# ESR_NM8032.net
KiCad netlist of a schematic drawn in EAGLE
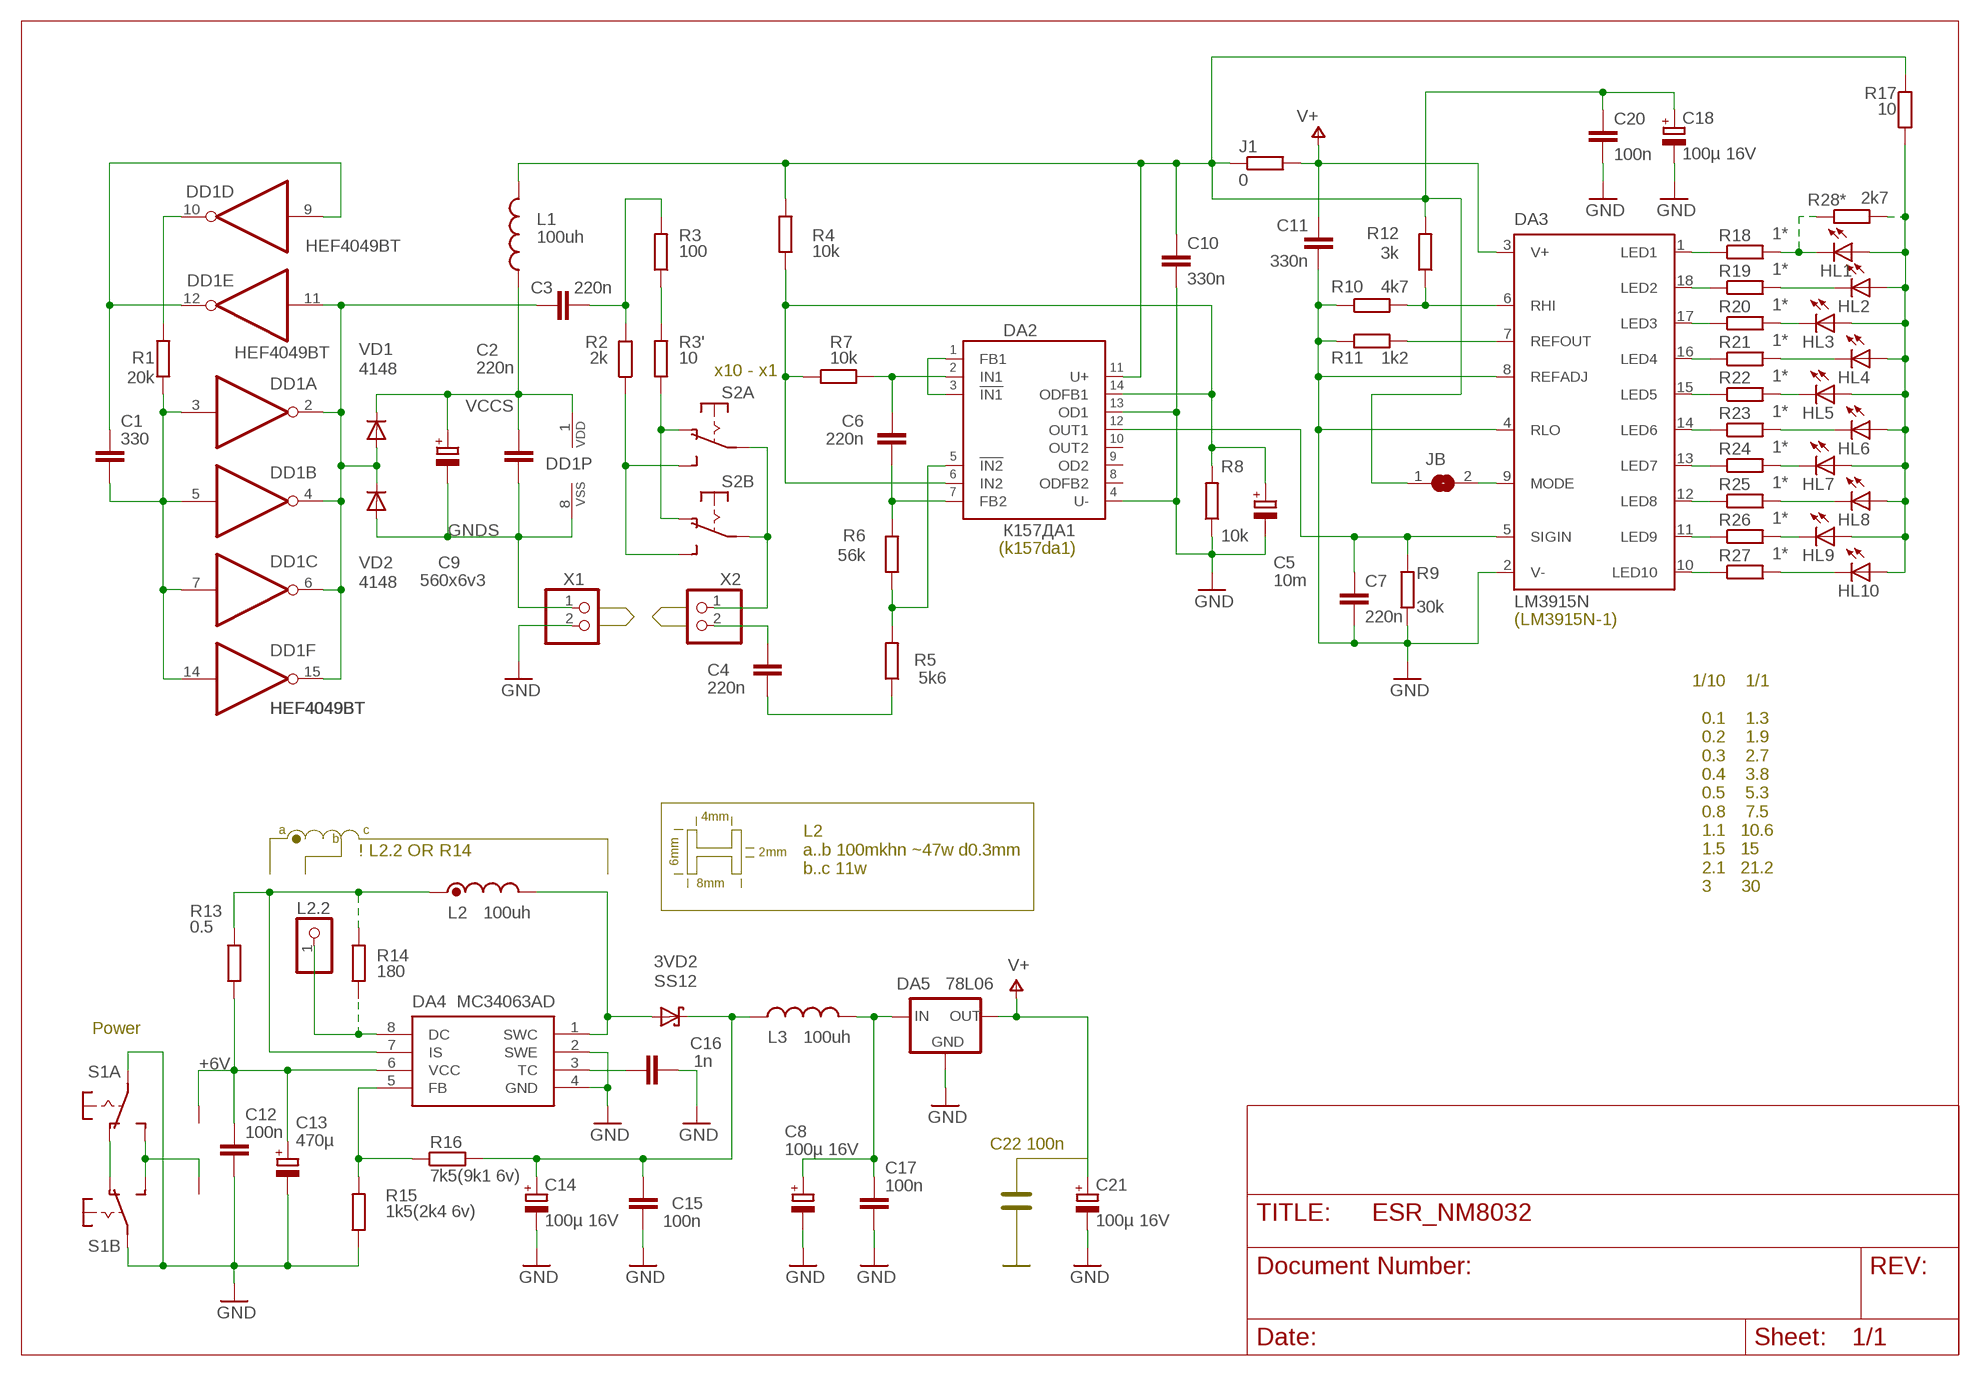
[diagram p0: schematic, sheet 1]

(export (version "E")
  (design (tool "Eeschema 10.0.6"))
  (components
    (comp (ref "3VD2")
      (value "SS12")
      (footprint "eagle-import:SMB")
      (libsource (lib "eagle-import") (part "SCHOTTKY-DIODESMD"))
    )
    (comp (ref "C1")
      (value "330")
      (footprint "eagle-import:C0805")
      (libsource (lib "eagle-import") (part "rcl_C-EUC0805"))
    )
    (comp (ref "C2")
      (value "220n")
      (footprint "eagle-import:C075-032X103")
      (libsource (lib "eagle-import") (part "rcl_C-EU075-032X103"))
    )
    (comp (ref "C3")
      (value "220n")
      (footprint "eagle-import:C0805")
      (libsource (lib "eagle-import") (part "rcl_C-EUC0805"))
    )
    (comp (ref "C4")
      (value "220n")
      (footprint "eagle-import:C0805")
      (libsource (lib "eagle-import") (part "rcl_C-EUC0805"))
    )
    (comp (ref "C5")
      (value "10m")
      (footprint "eagle-import:E2-5")
      (libsource (lib "eagle-import") (part "CPOL-EUE2-5"))
    )
    (comp (ref "C6")
      (value "220n")
      (footprint "eagle-import:C075-032X103")
      (libsource (lib "eagle-import") (part "rcl_C-EU075-032X103"))
    )
    (comp (ref "C7")
      (value "220n")
      (footprint "eagle-import:C0805")
      (libsource (lib "eagle-import") (part "rcl_C-EUC0805"))
    )
    (comp (ref "C8")
      (value "100µ 16V")
      (footprint "eagle-import:RCL_E2,5-5")
      (libsource (lib "eagle-import") (part "RCL_CPOL-EUE2.5-5"))
    )
    (comp (ref "C9")
      (value "560x6v3")
      (footprint "eagle-import:HWPROGUSB_RCL_E3,5-8")
      (libsource (lib "eagle-import") (part "HWPROGUSB_RCL_CPOL-EUE3.5-8"))
    )
    (comp (ref "C10")
      (value "330n")
      (footprint "eagle-import:C0805")
      (libsource (lib "eagle-import") (part "rcl_C-EUC0805"))
    )
    (comp (ref "C11")
      (value "330n")
      (footprint "eagle-import:C0805")
      (libsource (lib "eagle-import") (part "rcl_C-EUC0805"))
    )
    (comp (ref "C12")
      (value "100n")
      (footprint "eagle-import:C0805")
      (libsource (lib "eagle-import") (part "C-EUC0805"))
    )
    (comp (ref "C13")
      (value "470µ")
      (footprint "eagle-import:RCL_E2,5-7")
      (libsource (lib "eagle-import") (part "RCL_CPOL-EUE2.5-7"))
    )
    (comp (ref "C14")
      (value "100µ 16V")
      (footprint "eagle-import:RCL_E2,5-5")
      (libsource (lib "eagle-import") (part "RCL_CPOL-EUE2.5-5"))
    )
    (comp (ref "C15")
      (value "100n")
      (footprint "eagle-import:C0805")
      (libsource (lib "eagle-import") (part "rcl_C-EUC0805"))
    )
    (comp (ref "C16")
      (value "1n")
      (footprint "eagle-import:C0805")
      (libsource (lib "eagle-import") (part "rcl_C-EUC0805"))
    )
    (comp (ref "C17")
      (value "100n")
      (footprint "eagle-import:C0805")
      (libsource (lib "eagle-import") (part "rcl_C-EUC0805"))
    )
    (comp (ref "C18")
      (value "100µ 16V")
      (footprint "eagle-import:RCL_E2,5-5")
      (libsource (lib "eagle-import") (part "RCL_CPOL-EUE2.5-5"))
    )
    (comp (ref "C20")
      (value "100n")
      (footprint "eagle-import:C0805")
      (libsource (lib "eagle-import") (part "rcl_C-EUC0805"))
    )
    (comp (ref "C21")
      (value "100µ 16V")
      (footprint "eagle-import:RCL_E2,5-5")
      (libsource (lib "eagle-import") (part "RCL_CPOL-EUE2.5-5"))
    )
    (comp (ref "DA2")
      (value "К157ДА1")
      (footprint "eagle-import:DIL14")
      (libsource (lib "eagle-import") (part "K157DA1"))
    )
    (comp (ref "DA3")
      (value "LM3915N")
      (footprint "eagle-import:DIL18")
      (libsource (lib "eagle-import") (part "LM391N5"))
    )
    (comp (ref "DA4")
      (value "MC34063AD")
      (footprint "eagle-import:SOIC8")
      (libsource (lib "eagle-import") (part "MC34063AD"))
    )
    (comp (ref "DA5")
      (value "78L06")
      (footprint "eagle-import:SOT89R")
      (libsource (lib "eagle-import") (part "78LXX_SOT89"))
    )
    (comp (ref "DD1")
      (value "HEF4049BT")
      (footprint "eagle-import:SO16")
      (libsource (lib "eagle-import") (part "4049D"))
    )
    (comp (ref "HL1")
      (value "LED3MM")
      (footprint "eagle-import:LED3MM")
      (libsource (lib "eagle-import") (part "LED3MM"))
    )
    (comp (ref "HL2")
      (value "LED3MM")
      (footprint "eagle-import:LED3MM")
      (libsource (lib "eagle-import") (part "LED3MM"))
    )
    (comp (ref "HL3")
      (value "LED3MM")
      (footprint "eagle-import:LED3MM")
      (libsource (lib "eagle-import") (part "LED3MM"))
    )
    (comp (ref "HL4")
      (value "LED3MM")
      (footprint "eagle-import:LED3MM")
      (libsource (lib "eagle-import") (part "LED3MM"))
    )
    (comp (ref "HL5")
      (value "LED3MM")
      (footprint "eagle-import:LED3MM")
      (libsource (lib "eagle-import") (part "LED3MM"))
    )
    (comp (ref "HL6")
      (value "LED3MM")
      (footprint "eagle-import:LED3MM")
      (libsource (lib "eagle-import") (part "LED3MM"))
    )
    (comp (ref "HL7")
      (value "LED3MM")
      (footprint "eagle-import:LED3MM")
      (libsource (lib "eagle-import") (part "LED3MM"))
    )
    (comp (ref "HL8")
      (value "LED3MM")
      (footprint "eagle-import:LED3MM")
      (libsource (lib "eagle-import") (part "LED3MM"))
    )
    (comp (ref "HL9")
      (value "LED3MM")
      (footprint "eagle-import:LED3MM")
      (libsource (lib "eagle-import") (part "LED3MM"))
    )
    (comp (ref "HL10")
      (value "LED3MM")
      (footprint "eagle-import:LED3MM")
      (libsource (lib "eagle-import") (part "LED3MM"))
    )
    (comp (ref "J1")
      (value "0")
      (footprint "eagle-import:R1206W")
      (libsource (lib "eagle-import") (part "R-EU_R1206W"))
    )
    (comp (ref "JB") (value "SJ") (footprint "eagle-import:SJ") (libsource (lib "eagle-import") (part "SJ")))
    (comp (ref "L1")
      (value "100uh")
      (footprint "eagle-import:0207_10")
      (libsource (lib "eagle-import") (part "L-US0207/10"))
    )
    (comp (ref "L2")
      (value "100uh")
      (footprint "eagle-import:0204_7")
      (libsource (lib "eagle-import") (part "L-US0204/7"))
    )
    (comp (ref "L2.2")
      (value "PINHD-1X1")
      (footprint "eagle-import:1X01")
      (libsource (lib "eagle-import") (part "PINHD-1X1"))
    )
    (comp (ref "L3")
      (value "100uh")
      (footprint "eagle-import:0207_10")
      (libsource (lib "eagle-import") (part "L-US0207/10"))
    )
    (comp (ref "R1")
      (value "20k")
      (footprint "eagle-import:M0805")
      (libsource (lib "eagle-import") (part "R-EU_M0805"))
    )
    (comp (ref "R2")
      (value "2k")
      (footprint "eagle-import:M0805")
      (libsource (lib "eagle-import") (part "R-EU_M0805"))
    )
    (comp (ref "R3")
      (value "100")
      (footprint "eagle-import:M0805")
      (libsource (lib "eagle-import") (part "R-EU_M0805"))
    )
    (comp (ref "R3'")
      (value "10")
      (footprint "eagle-import:M0805")
      (libsource (lib "eagle-import") (part "R-EU_M0805"))
    )
    (comp (ref "R4")
      (value "10k")
      (footprint "eagle-import:R0805")
      (libsource (lib "eagle-import") (part "R-EU_R0805"))
    )
    (comp (ref "R5")
      (value "5k6")
      (footprint "eagle-import:M0805")
      (libsource (lib "eagle-import") (part "R-EU_M0805"))
    )
    (comp (ref "R6")
      (value "56k")
      (footprint "eagle-import:R0805")
      (libsource (lib "eagle-import") (part "R-EU_R0805"))
    )
    (comp (ref "R7")
      (value "10k")
      (footprint "eagle-import:R0805")
      (libsource (lib "eagle-import") (part "R-EU_R0805"))
    )
    (comp (ref "R8")
      (value "10k")
      (footprint "eagle-import:R0805")
      (libsource (lib "eagle-import") (part "R-EU_R0805"))
    )
    (comp (ref "R9")
      (value "30k")
      (footprint "eagle-import:R0805")
      (libsource (lib "eagle-import") (part "R-EU_R0805"))
    )
    (comp (ref "R10")
      (value "4k7")
      (footprint "eagle-import:R0805")
      (libsource (lib "eagle-import") (part "R-EU_R0805"))
    )
    (comp (ref "R11")
      (value "1k2")
      (footprint "eagle-import:R0805")
      (libsource (lib "eagle-import") (part "R-EU_R0805"))
    )
    (comp (ref "R12")
      (value "3k")
      (footprint "eagle-import:R0805")
      (libsource (lib "eagle-import") (part "R-EU_R0805"))
    )
    (comp (ref "R13")
      (value "0.5")
      (footprint "eagle-import:M1206")
      (libsource (lib "eagle-import") (part "R-EU_M1206"))
    )
    (comp (ref "R14")
      (value "180")
      (footprint "eagle-import:M0805")
      (libsource (lib "eagle-import") (part "R-EU_M0805"))
    )
    (comp (ref "R15")
      (value "1k5(2k4 6v)")
      (footprint "eagle-import:M0805")
      (libsource (lib "eagle-import") (part "R-EU_M0805"))
    )
    (comp (ref "R16")
      (value "7k5(9k1 6v)")
      (footprint "eagle-import:M0805")
      (libsource (lib "eagle-import") (part "R-EU_M0805"))
    )
    (comp (ref "R17")
      (value "10")
      (footprint "eagle-import:R0805")
      (libsource (lib "eagle-import") (part "R-EU_R0805"))
    )
    (comp (ref "R18")
      (value "1*")
      (footprint "eagle-import:R0805")
      (libsource (lib "eagle-import") (part "R-EU_R0805"))
    )
    (comp (ref "R19")
      (value "1*")
      (footprint "eagle-import:R0805")
      (libsource (lib "eagle-import") (part "R-EU_R0805"))
    )
    (comp (ref "R20")
      (value "1*")
      (footprint "eagle-import:R0805")
      (libsource (lib "eagle-import") (part "R-EU_R0805"))
    )
    (comp (ref "R21")
      (value "1*")
      (footprint "eagle-import:R0805")
      (libsource (lib "eagle-import") (part "R-EU_R0805"))
    )
    (comp (ref "R22")
      (value "1*")
      (footprint "eagle-import:R0805")
      (libsource (lib "eagle-import") (part "R-EU_R0805"))
    )
    (comp (ref "R23")
      (value "1*")
      (footprint "eagle-import:R0805")
      (libsource (lib "eagle-import") (part "R-EU_R0805"))
    )
    (comp (ref "R24")
      (value "1*")
      (footprint "eagle-import:R0805")
      (libsource (lib "eagle-import") (part "R-EU_R0805"))
    )
    (comp (ref "R25")
      (value "1*")
      (footprint "eagle-import:R0805")
      (libsource (lib "eagle-import") (part "R-EU_R0805"))
    )
    (comp (ref "R26")
      (value "1*")
      (footprint "eagle-import:R0805")
      (libsource (lib "eagle-import") (part "R-EU_R0805"))
    )
    (comp (ref "R27")
      (value "1*")
      (footprint "eagle-import:R0805")
      (libsource (lib "eagle-import") (part "R-EU_R0805"))
    )
    (comp (ref "R28*")
      (value "2k7")
      (footprint "eagle-import:R0805")
      (libsource (lib "eagle-import") (part "R-EU_R0805"))
    )
    (comp (ref "S1")
      (value "SWITCH9X4")
      (footprint "eagle-import:SWITCH9X4")
      (libsource (lib "eagle-import") (part "SWITCH9X4"))
    )
    (comp (ref "S2")
      (value "SWITCH9X4")
      (footprint "eagle-import:SWITCH9X4")
      (libsource (lib "eagle-import") (part "SWITCH9X4"))
    )
    (comp (ref "U$2") (value "B-") (footprint "eagle-import:B-") (libsource (lib "eagle-import") (part "B-")))
    (comp (ref "U$4") (value "B+") (footprint "eagle-import:B+") (libsource (lib "eagle-import") (part "B+")))
    (comp (ref "VD1")
      (value "4148")
      (footprint "eagle-import:SOD80C")
      (libsource (lib "eagle-import") (part "DIODE-SOD80C"))
    )
    (comp (ref "VD2")
      (value "4148")
      (footprint "eagle-import:SOD80C")
      (libsource (lib "eagle-import") (part "DIODE-SOD80C"))
    )
    (comp (ref "X1")
      (value "PINHD-1X2/2")
      (footprint "eagle-import:1X02")
      (libsource (lib "eagle-import") (part "PINHD-1X2/2"))
    )
    (comp (ref "X2")
      (value "PINHD-1X2/2")
      (footprint "eagle-import:1X02")
      (libsource (lib "eagle-import") (part "PINHD-1X2/2"))
    )
  )
  (nets
    (net (code "1") (name "/+6V") (class "Default")
      (node (ref "C12") (pin "1") (pinfunction "1_1") (pintype "passive"))
      (node (ref "C13") (pin "+") (pinfunction "+_+") (pintype "passive"))
      (node (ref "DA4") (pin "6") (pinfunction "VCC_6") (pintype "passive"))
      (node (ref "R13") (pin "1") (pinfunction "1_1") (pintype "passive"))
      (node (ref "U$4") (pin "P$1") (pinfunction "P$1_P$1") (pintype "bidirectional"))
    )
    (net (code "2") (name "/GNDS") (class "Default")
      (node (ref "C2") (pin "2") (pinfunction "2_2") (pintype "passive"))
      (node (ref "C9") (pin "-") (pinfunction "-_-") (pintype "passive"))
      (node (ref "DD1") (pin "8") (pinfunction "VSS_8") (pintype "power_in"))
      (node (ref "VD2") (pin "A") (pinfunction "A_A") (pintype "passive"))
      (node (ref "X1") (pin "1") (pinfunction "1_1") (pintype "passive"))
    )
    (net (code "3") (name "/VCCS") (class "Default")
      (node (ref "C2") (pin "1") (pinfunction "1_1") (pintype "passive"))
      (node (ref "C9") (pin "+") (pinfunction "+_+") (pintype "passive"))
      (node (ref "DD1") (pin "1") (pinfunction "VDD_1") (pintype "power_in"))
      (node (ref "L1") (pin "1") (pinfunction "1_1") (pintype "passive"))
      (node (ref "VD1") (pin "C") (pinfunction "C_C") (pintype "passive"))
    )
    (net (code "4") (name "GND") (class "Default")
      (node (ref "C10") (pin "2") (pinfunction "2_2") (pintype "passive"))
      (node (ref "C11") (pin "2") (pinfunction "2_2") (pintype "passive"))
      (node (ref "C12") (pin "2") (pinfunction "2_2") (pintype "passive"))
      (node (ref "C13") (pin "-") (pinfunction "-_-") (pintype "passive"))
      (node (ref "C14") (pin "-") (pinfunction "-_-") (pintype "passive"))
      (node (ref "C15") (pin "1") (pinfunction "1_1") (pintype "passive"))
      (node (ref "C16") (pin "2") (pinfunction "2_2") (pintype "passive"))
      (node (ref "C17") (pin "2") (pinfunction "2_2") (pintype "passive"))
      (node (ref "C18") (pin "-") (pinfunction "-_-") (pintype "passive"))
      (node (ref "C20") (pin "2") (pinfunction "2_2") (pintype "passive"))
      (node (ref "C21") (pin "-") (pinfunction "-_-") (pintype "passive"))
      (node (ref "C5") (pin "-") (pinfunction "-_-") (pintype "passive"))
      (node (ref "C7") (pin "2") (pinfunction "2_2") (pintype "passive"))
      (node (ref "C8") (pin "-") (pinfunction "-_-") (pintype "passive"))
      (node (ref "DA2") (pin "13") (pinfunction "OD1_13") (pintype "passive"))
      (node (ref "DA2") (pin "4") (pinfunction "U-_4") (pintype "passive"))
      (node (ref "DA3") (pin "2") (pinfunction "V-_2") (pintype "power_in"))
      (node (ref "DA3") (pin "4") (pinfunction "RLO_4") (pintype "input"))
      (node (ref "DA3") (pin "8") (pinfunction "REFADJ_8") (pintype "passive"))
      (node (ref "DA4") (pin "2") (pinfunction "SWE_2") (pintype "passive"))
      (node (ref "DA4") (pin "4") (pinfunction "GND_4") (pintype "passive"))
      (node (ref "DA5") (pin "3") (pinfunction "GND_3") (pintype "input"))
      (node (ref "DA5") (pin "4") (pinfunction "GND_4") (pintype "input"))
      (node (ref "R10") (pin "1") (pinfunction "1_1") (pintype "passive"))
      (node (ref "R11") (pin "1") (pinfunction "1_1") (pintype "passive"))
      (node (ref "R15") (pin "1") (pinfunction "1_1") (pintype "passive"))
      (node (ref "R8") (pin "1") (pinfunction "1_1") (pintype "passive"))
      (node (ref "R9") (pin "1") (pinfunction "1_1") (pintype "passive"))
      (node (ref "S1") (pin "10") (pinfunction "P_10") (pintype "passive"))
      (node (ref "S1") (pin "20") (pinfunction "P_20") (pintype "passive"))
      (node (ref "X1") (pin "2") (pinfunction "2_2") (pintype "passive"))
    )
    (net (code "5") (name "Net-(3VD2-PadC)") (class "Default")
      (node (ref "3VD2") (pin "C") (pinfunction "C_C") (pintype "passive"))
      (node (ref "C14") (pin "+") (pinfunction "+_+") (pintype "passive"))
      (node (ref "C15") (pin "2") (pinfunction "2_2") (pintype "passive"))
      (node (ref "L3") (pin "1") (pinfunction "1_1") (pintype "passive"))
      (node (ref "R16") (pin "2") (pinfunction "2_2") (pintype "passive"))
    )
    (net (code "6") (name "Net-(C3-Pad2)") (class "Default")
      (node (ref "C3") (pin "2") (pinfunction "2_2") (pintype "passive"))
      (node (ref "R2") (pin "2") (pinfunction "2_2") (pintype "passive"))
      (node (ref "R3") (pin "2") (pinfunction "2_2") (pintype "passive"))
    )
    (net (code "7") (name "Net-(C4-Pad1)") (class "Default")
      (node (ref "C4") (pin "1") (pinfunction "1_1") (pintype "passive"))
      (node (ref "X2") (pin "2") (pinfunction "2_2") (pintype "passive"))
    )
    (net (code "8") (name "Net-(C4-Pad2)") (class "Default")
      (node (ref "C4") (pin "2") (pinfunction "2_2") (pintype "passive"))
      (node (ref "R5") (pin "1") (pinfunction "1_1") (pintype "passive"))
    )
    (net (code "9") (name "Net-(DA2-FB1)") (class "Default")
      (node (ref "DA2") (pin "1") (pinfunction "FB1_1") (pintype "passive"))
      (node (ref "DA2") (pin "3") (pinfunction "~{IN1}_3") (pintype "passive"))
    )
    (net (code "10") (name "Net-(DA2-FB2)") (class "Default")
      (node (ref "C6") (pin "2") (pinfunction "2_2") (pintype "passive"))
      (node (ref "DA2") (pin "7") (pinfunction "FB2_7") (pintype "passive"))
      (node (ref "R6") (pin "2") (pinfunction "2_2") (pintype "passive"))
    )
    (net (code "11") (name "Net-(DA2-IN1)") (class "Default")
      (node (ref "C6") (pin "1") (pinfunction "1_1") (pintype "passive"))
      (node (ref "DA2") (pin "2") (pinfunction "IN1_2") (pintype "passive"))
      (node (ref "R7") (pin "2") (pinfunction "2_2") (pintype "passive"))
    )
    (net (code "12") (name "Net-(DA2-IN2)") (class "Default")
      (node (ref "C5") (pin "+") (pinfunction "+_+") (pintype "passive"))
      (node (ref "DA2") (pin "14") (pinfunction "ODFB1_14") (pintype "passive"))
      (node (ref "DA2") (pin "6") (pinfunction "IN2_6") (pintype "passive"))
      (node (ref "R4") (pin "1") (pinfunction "1_1") (pintype "passive"))
      (node (ref "R7") (pin "1") (pinfunction "1_1") (pintype "passive"))
      (node (ref "R8") (pin "2") (pinfunction "2_2") (pintype "passive"))
    )
    (net (code "13") (name "Net-(DA2-OUT1)") (class "Default")
      (node (ref "C7") (pin "1") (pinfunction "1_1") (pintype "passive"))
      (node (ref "DA2") (pin "12") (pinfunction "OUT1_12") (pintype "passive"))
      (node (ref "DA3") (pin "5") (pinfunction "SIGIN_5") (pintype "input"))
      (node (ref "R9") (pin "2") (pinfunction "2_2") (pintype "passive"))
    )
    (net (code "14") (name "Net-(DA2-U+)") (class "Default")
      (node (ref "C10") (pin "1") (pinfunction "1_1") (pintype "passive"))
      (node (ref "C18") (pin "+") (pinfunction "+_+") (pintype "passive"))
      (node (ref "C20") (pin "1") (pinfunction "1_1") (pintype "passive"))
      (node (ref "DA2") (pin "11") (pinfunction "U+_11") (pintype "passive"))
      (node (ref "J1") (pin "1") (pinfunction "1_1") (pintype "passive"))
      (node (ref "JB") (pin "1") (pinfunction "1_1") (pintype "passive"))
      (node (ref "L1") (pin "2") (pinfunction "2_2") (pintype "passive"))
      (node (ref "R12") (pin "2") (pinfunction "2_2") (pintype "passive"))
      (node (ref "R17") (pin "1") (pinfunction "1_1") (pintype "passive"))
      (node (ref "R4") (pin "2") (pinfunction "2_2") (pintype "passive"))
    )
    (net (code "15") (name "Net-(DA2-~{IN2})") (class "Default")
      (node (ref "DA2") (pin "5") (pinfunction "~{IN2}_5") (pintype "passive"))
      (node (ref "R5") (pin "2") (pinfunction "2_2") (pintype "passive"))
      (node (ref "R6") (pin "1") (pinfunction "1_1") (pintype "passive"))
    )
    (net (code "16") (name "Net-(DA3-LED1)") (class "Default")
      (node (ref "DA3") (pin "1") (pinfunction "LED1_1") (pintype "output"))
      (node (ref "R18") (pin "1") (pinfunction "1_1") (pintype "passive"))
    )
    (net (code "17") (name "Net-(DA3-LED2)") (class "Default")
      (node (ref "DA3") (pin "18") (pinfunction "LED2_18") (pintype "output"))
      (node (ref "R19") (pin "1") (pinfunction "1_1") (pintype "passive"))
    )
    (net (code "18") (name "Net-(DA3-LED3)") (class "Default")
      (node (ref "DA3") (pin "17") (pinfunction "LED3_17") (pintype "output"))
      (node (ref "R20") (pin "1") (pinfunction "1_1") (pintype "passive"))
    )
    (net (code "19") (name "Net-(DA3-LED4)") (class "Default")
      (node (ref "DA3") (pin "16") (pinfunction "LED4_16") (pintype "output"))
      (node (ref "R21") (pin "1") (pinfunction "1_1") (pintype "passive"))
    )
    (net (code "20") (name "Net-(DA3-LED5)") (class "Default")
      (node (ref "DA3") (pin "15") (pinfunction "LED5_15") (pintype "output"))
      (node (ref "R22") (pin "1") (pinfunction "1_1") (pintype "passive"))
    )
    (net (code "21") (name "Net-(DA3-LED6)") (class "Default")
      (node (ref "DA3") (pin "14") (pinfunction "LED6_14") (pintype "output"))
      (node (ref "R23") (pin "1") (pinfunction "1_1") (pintype "passive"))
    )
    (net (code "22") (name "Net-(DA3-LED7)") (class "Default")
      (node (ref "DA3") (pin "13") (pinfunction "LED7_13") (pintype "output"))
      (node (ref "R24") (pin "1") (pinfunction "1_1") (pintype "passive"))
    )
    (net (code "23") (name "Net-(DA3-LED8)") (class "Default")
      (node (ref "DA3") (pin "12") (pinfunction "LED8_12") (pintype "output"))
      (node (ref "R25") (pin "1") (pinfunction "1_1") (pintype "passive"))
    )
    (net (code "24") (name "Net-(DA3-LED9)") (class "Default")
      (node (ref "DA3") (pin "11") (pinfunction "LED9_11") (pintype "output"))
      (node (ref "R26") (pin "1") (pinfunction "1_1") (pintype "passive"))
    )
    (net (code "25") (name "Net-(DA3-LED10)") (class "Default")
      (node (ref "DA3") (pin "10") (pinfunction "LED10_10") (pintype "output"))
      (node (ref "R27") (pin "1") (pinfunction "1_1") (pintype "passive"))
    )
    (net (code "26") (name "Net-(DA3-MODE)") (class "Default")
      (node (ref "DA3") (pin "9") (pinfunction "MODE_9") (pintype "input"))
      (node (ref "JB") (pin "2") (pinfunction "2_2") (pintype "passive"))
    )
    (net (code "27") (name "Net-(DA3-REFOUT)") (class "Default")
      (node (ref "DA3") (pin "7") (pinfunction "REFOUT_7") (pintype "output"))
      (node (ref "R11") (pin "2") (pinfunction "2_2") (pintype "passive"))
    )
    (net (code "28") (name "Net-(DA3-RHI)") (class "Default")
      (node (ref "DA3") (pin "6") (pinfunction "RHI_6") (pintype "input"))
      (node (ref "R10") (pin "2") (pinfunction "2_2") (pintype "passive"))
      (node (ref "R12") (pin "1") (pinfunction "1_1") (pintype "passive"))
    )
    (net (code "29") (name "Net-(DA4-DC)") (class "Default")
      (node (ref "DA4") (pin "8") (pinfunction "DC_8") (pintype "passive"))
      (node (ref "L2.2") (pin "1") (pinfunction "1_1") (pintype "passive"))
      (node (ref "R14") (pin "1") (pinfunction "1_1") (pintype "passive"))
    )
    (net (code "30") (name "Net-(DA4-FB)") (class "Default")
      (node (ref "DA4") (pin "5") (pinfunction "FB_5") (pintype "passive"))
      (node (ref "R15") (pin "2") (pinfunction "2_2") (pintype "passive"))
      (node (ref "R16") (pin "1") (pinfunction "1_1") (pintype "passive"))
    )
    (net (code "31") (name "Net-(DA4-IS)") (class "Default")
      (node (ref "DA4") (pin "7") (pinfunction "IS_7") (pintype "passive"))
      (node (ref "L2") (pin "1") (pinfunction "1_1") (pintype "passive"))
      (node (ref "R13") (pin "2") (pinfunction "2_2") (pintype "passive"))
      (node (ref "R14") (pin "2") (pinfunction "2_2") (pintype "passive"))
    )
    (net (code "32") (name "Net-(DA4-SWC)") (class "Default")
      (node (ref "3VD2") (pin "A") (pinfunction "A_A") (pintype "passive"))
      (node (ref "DA4") (pin "1") (pinfunction "SWC_1") (pintype "passive"))
      (node (ref "L2") (pin "2") (pinfunction "2_2") (pintype "passive"))
    )
    (net (code "33") (name "Net-(DA4-TC)") (class "Default")
      (node (ref "C16") (pin "1") (pinfunction "1_1") (pintype "passive"))
      (node (ref "DA4") (pin "3") (pinfunction "TC_3") (pintype "passive"))
    )
    (net (code "34") (name "Net-(DA5-IN)") (class "Default")
      (node (ref "C17") (pin "1") (pinfunction "1_1") (pintype "passive"))
      (node (ref "C8") (pin "+") (pinfunction "+_+") (pintype "passive"))
      (node (ref "DA5") (pin "1") (pinfunction "IN_1") (pintype "input"))
      (node (ref "L3") (pin "2") (pinfunction "2_2") (pintype "passive"))
    )
    (net (code "35") (name "Net-(DD1A-I)") (class "Default")
      (node (ref "C1") (pin "2") (pinfunction "2_2") (pintype "passive"))
      (node (ref "DD1") (pin "14") (pinfunction "I_14") (pintype "input"))
      (node (ref "DD1") (pin "3") (pinfunction "I_3") (pintype "input"))
      (node (ref "DD1") (pin "5") (pinfunction "I_5") (pintype "input"))
      (node (ref "DD1") (pin "7") (pinfunction "I_7") (pintype "input"))
      (node (ref "R1") (pin "1") (pinfunction "1_1") (pintype "passive"))
    )
    (net (code "36") (name "Net-(DD1A-O)") (class "Default")
      (node (ref "C3") (pin "1") (pinfunction "1_1") (pintype "passive"))
      (node (ref "DD1") (pin "11") (pinfunction "I_11") (pintype "input"))
      (node (ref "DD1") (pin "15") (pinfunction "O_15") (pintype "output"))
      (node (ref "DD1") (pin "2") (pinfunction "O_2") (pintype "output"))
      (node (ref "DD1") (pin "4") (pinfunction "O_4") (pintype "output"))
      (node (ref "DD1") (pin "6") (pinfunction "O_6") (pintype "output"))
      (node (ref "VD1") (pin "A") (pinfunction "A_A") (pintype "passive"))
      (node (ref "VD2") (pin "C") (pinfunction "C_C") (pintype "passive"))
    )
    (net (code "37") (name "Net-(DD1D-I)") (class "Default")
      (node (ref "C1") (pin "1") (pinfunction "1_1") (pintype "passive"))
      (node (ref "DD1") (pin "12") (pinfunction "O_12") (pintype "output"))
      (node (ref "DD1") (pin "9") (pinfunction "I_9") (pintype "input"))
    )
    (net (code "38") (name "Net-(DD1D-O)") (class "Default")
      (node (ref "DD1") (pin "10") (pinfunction "O_10") (pintype "output"))
      (node (ref "R1") (pin "2") (pinfunction "2_2") (pintype "passive"))
    )
    (net (code "39") (name "Net-(HL1-C)") (class "Default")
      (node (ref "HL1") (pin "K") (pinfunction "C_K") (pintype "passive"))
      (node (ref "R18") (pin "2") (pinfunction "2_2") (pintype "passive"))
      (node (ref "R28*") (pin "1") (pinfunction "1_1") (pintype "passive"))
    )
    (net (code "40") (name "Net-(HL1-PadA)") (class "Default")
      (node (ref "HL1") (pin "A") (pinfunction "A_A") (pintype "passive"))
      (node (ref "HL10") (pin "A") (pinfunction "A_A") (pintype "passive"))
      (node (ref "HL2") (pin "A") (pinfunction "A_A") (pintype "passive"))
      (node (ref "HL3") (pin "A") (pinfunction "A_A") (pintype "passive"))
      (node (ref "HL4") (pin "A") (pinfunction "A_A") (pintype "passive"))
      (node (ref "HL5") (pin "A") (pinfunction "A_A") (pintype "passive"))
      (node (ref "HL6") (pin "A") (pinfunction "A_A") (pintype "passive"))
      (node (ref "HL7") (pin "A") (pinfunction "A_A") (pintype "passive"))
      (node (ref "HL8") (pin "A") (pinfunction "A_A") (pintype "passive"))
      (node (ref "HL9") (pin "A") (pinfunction "A_A") (pintype "passive"))
      (node (ref "R17") (pin "2") (pinfunction "2_2") (pintype "passive"))
      (node (ref "R28*") (pin "2") (pinfunction "2_2") (pintype "passive"))
    )
    (net (code "41") (name "Net-(HL2-C)") (class "Default")
      (node (ref "HL2") (pin "K") (pinfunction "C_K") (pintype "passive"))
      (node (ref "R19") (pin "2") (pinfunction "2_2") (pintype "passive"))
    )
    (net (code "42") (name "Net-(HL3-C)") (class "Default")
      (node (ref "HL3") (pin "K") (pinfunction "C_K") (pintype "passive"))
      (node (ref "R20") (pin "2") (pinfunction "2_2") (pintype "passive"))
    )
    (net (code "43") (name "Net-(HL4-C)") (class "Default")
      (node (ref "HL4") (pin "K") (pinfunction "C_K") (pintype "passive"))
      (node (ref "R21") (pin "2") (pinfunction "2_2") (pintype "passive"))
    )
    (net (code "44") (name "Net-(HL5-C)") (class "Default")
      (node (ref "HL5") (pin "K") (pinfunction "C_K") (pintype "passive"))
      (node (ref "R22") (pin "2") (pinfunction "2_2") (pintype "passive"))
    )
    (net (code "45") (name "Net-(HL6-C)") (class "Default")
      (node (ref "HL6") (pin "K") (pinfunction "C_K") (pintype "passive"))
      (node (ref "R23") (pin "2") (pinfunction "2_2") (pintype "passive"))
    )
    (net (code "46") (name "Net-(HL7-C)") (class "Default")
      (node (ref "HL7") (pin "K") (pinfunction "C_K") (pintype "passive"))
      (node (ref "R24") (pin "2") (pinfunction "2_2") (pintype "passive"))
    )
    (net (code "47") (name "Net-(HL8-C)") (class "Default")
      (node (ref "HL8") (pin "K") (pinfunction "C_K") (pintype "passive"))
      (node (ref "R25") (pin "2") (pinfunction "2_2") (pintype "passive"))
    )
    (net (code "48") (name "Net-(HL9-C)") (class "Default")
      (node (ref "HL9") (pin "K") (pinfunction "C_K") (pintype "passive"))
      (node (ref "R26") (pin "2") (pinfunction "2_2") (pintype "passive"))
    )
    (net (code "49") (name "Net-(HL10-C)") (class "Default")
      (node (ref "HL10") (pin "K") (pinfunction "C_K") (pintype "passive"))
      (node (ref "R27") (pin "2") (pinfunction "2_2") (pintype "passive"))
    )
    (net (code "50") (name "Net-(R3'-Pad2)") (class "Default")
      (node (ref "R3") (pin "1") (pinfunction "1_1") (pintype "passive"))
      (node (ref "R3'") (pin "2") (pinfunction "2_2") (pintype "passive"))
    )
    (net (code "51") (name "Net-(S1A-O)") (class "Default")
      (node (ref "S1") (pin "11") (pinfunction "O_11") (pintype "passive"))
      (node (ref "S1") (pin "21") (pinfunction "O_21") (pintype "passive"))
    )
    (net (code "52") (name "Net-(S1A-S)") (class "Default")
      (node (ref "S1") (pin "12") (pinfunction "S_12") (pintype "passive"))
      (node (ref "S1") (pin "22") (pinfunction "S_22") (pintype "passive"))
      (node (ref "U$2") (pin "P$1") (pinfunction "P$1_P$1") (pintype "bidirectional"))
    )
    (net (code "53") (name "Net-(S2A-O)") (class "Default")
      (node (ref "R3'") (pin "1") (pinfunction "1_1") (pintype "passive"))
      (node (ref "S2") (pin "11") (pinfunction "O_11") (pintype "passive"))
      (node (ref "S2") (pin "21") (pinfunction "O_21") (pintype "passive"))
    )
    (net (code "54") (name "Net-(S2A-P)") (class "Default")
      (node (ref "S2") (pin "10") (pinfunction "P_10") (pintype "passive"))
      (node (ref "S2") (pin "20") (pinfunction "P_20") (pintype "passive"))
      (node (ref "X2") (pin "1") (pinfunction "1_1") (pintype "passive"))
    )
    (net (code "55") (name "Net-(S2A-S)") (class "Default")
      (node (ref "R2") (pin "1") (pinfunction "1_1") (pintype "passive"))
      (node (ref "S2") (pin "12") (pinfunction "S_12") (pintype "passive"))
      (node (ref "S2") (pin "22") (pinfunction "S_22") (pintype "passive"))
    )
    (net (code "56") (name "V+") (class "Default")
      (node (ref "C11") (pin "1") (pinfunction "1_1") (pintype "passive"))
      (node (ref "C21") (pin "+") (pinfunction "+_+") (pintype "passive"))
      (node (ref "DA3") (pin "3") (pinfunction "V+_3") (pintype "power_in"))
      (node (ref "DA5") (pin "2") (pinfunction "OUT_2") (pintype "passive"))
      (node (ref "J1") (pin "2") (pinfunction "2_2") (pintype "passive"))
    )
    (net (code "57") (name "unconnected-(DA2-OD2-Pad9)") (class "Default")
      (node (ref "DA2") (pin "9") (pinfunction "OD2_9") (pintype "passive"))
    )
    (net (code "58") (name "unconnected-(DA2-ODFB2-Pad8)") (class "Default")
      (node (ref "DA2") (pin "8") (pinfunction "ODFB2_8") (pintype "passive"))
    )
    (net (code "59") (name "unconnected-(DA2-OUT2-Pad10)") (class "Default")
      (node (ref "DA2") (pin "10") (pinfunction "OUT2_10") (pintype "passive"))
    )
  )
)
